# NeoDigito_Medio.net
KiCad netlist of a schematic drawn in EAGLE
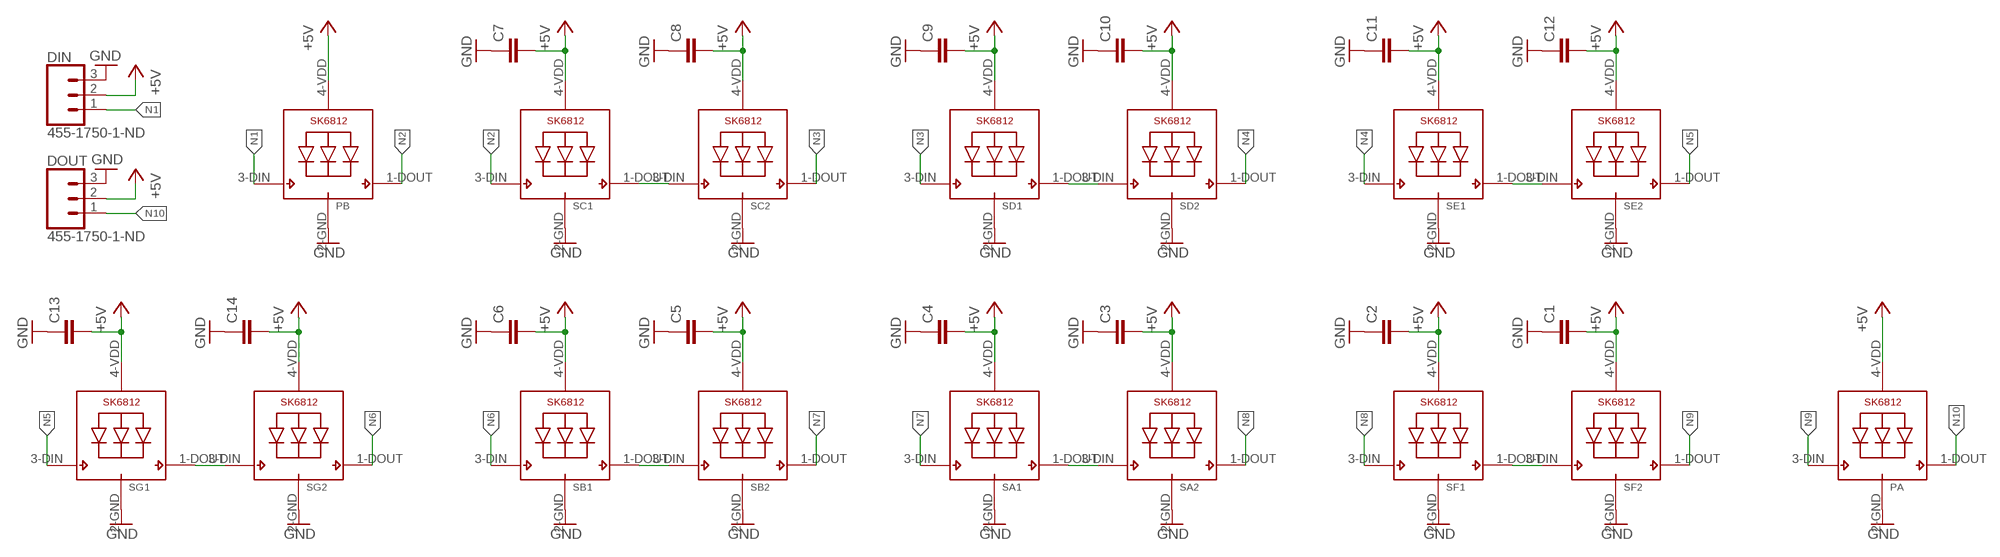
[diagram p0: schematic, sheet 1]

(export (version "E")
  (design (tool "Eeschema 10.0.6"))
  (components
    (comp (ref "C1")
      (value "C-EUC0805")
      (footprint "eagle-import:C0805")
      (libsource (lib "eagle-import") (part "C-EUC0805"))
    )
    (comp (ref "C2")
      (value "C-EUC0805")
      (footprint "eagle-import:C0805")
      (libsource (lib "eagle-import") (part "C-EUC0805"))
    )
    (comp (ref "C3")
      (value "C-EUC0805")
      (footprint "eagle-import:C0805")
      (libsource (lib "eagle-import") (part "C-EUC0805"))
    )
    (comp (ref "C4")
      (value "C-EUC0805")
      (footprint "eagle-import:C0805")
      (libsource (lib "eagle-import") (part "C-EUC0805"))
    )
    (comp (ref "C5")
      (value "C-EUC0805")
      (footprint "eagle-import:C0805")
      (libsource (lib "eagle-import") (part "C-EUC0805"))
    )
    (comp (ref "C6")
      (value "C-EUC0805")
      (footprint "eagle-import:C0805")
      (libsource (lib "eagle-import") (part "C-EUC0805"))
    )
    (comp (ref "C7")
      (value "C-EUC0805")
      (footprint "eagle-import:C0805")
      (libsource (lib "eagle-import") (part "C-EUC0805"))
    )
    (comp (ref "C8")
      (value "C-EUC0805")
      (footprint "eagle-import:C0805")
      (libsource (lib "eagle-import") (part "C-EUC0805"))
    )
    (comp (ref "C9")
      (value "C-EUC0805")
      (footprint "eagle-import:C0805")
      (libsource (lib "eagle-import") (part "C-EUC0805"))
    )
    (comp (ref "C10")
      (value "C-EUC0805")
      (footprint "eagle-import:C0805")
      (libsource (lib "eagle-import") (part "C-EUC0805"))
    )
    (comp (ref "C11")
      (value "C-EUC0805")
      (footprint "eagle-import:C0805")
      (libsource (lib "eagle-import") (part "C-EUC0805"))
    )
    (comp (ref "C12")
      (value "C-EUC0805")
      (footprint "eagle-import:C0805")
      (libsource (lib "eagle-import") (part "C-EUC0805"))
    )
    (comp (ref "C13")
      (value "C-EUC0805")
      (footprint "eagle-import:C0805")
      (libsource (lib "eagle-import") (part "C-EUC0805"))
    )
    (comp (ref "C14")
      (value "C-EUC0805")
      (footprint "eagle-import:C0805")
      (libsource (lib "eagle-import") (part "C-EUC0805"))
    )
    (comp (ref "DIN")
      (value "455-1750-1-ND")
      (footprint "eagle-import:1X03")
      (libsource (lib "eagle-import") (part "CONN_03"))
    )
    (comp (ref "DOUT")
      (value "455-1750-1-ND")
      (footprint "eagle-import:1X03_NO_SILK")
      (libsource (lib "eagle-import") (part "CONN_031X03_NO_SILK"))
    )
    (comp (ref "PA")
      (value "SK6812_3535")
      (footprint "eagle-import:LED3535")
      (libsource (lib "eagle-import") (part "SK6812_3535"))
    )
    (comp (ref "PB")
      (value "SK6812_3535")
      (footprint "eagle-import:LED3535")
      (libsource (lib "eagle-import") (part "SK6812_3535"))
    )
    (comp (ref "SA1")
      (value "SK6812_3535")
      (footprint "eagle-import:LED3535")
      (libsource (lib "eagle-import") (part "SK6812_3535"))
    )
    (comp (ref "SA2")
      (value "SK6812_3535")
      (footprint "eagle-import:LED3535")
      (libsource (lib "eagle-import") (part "SK6812_3535"))
    )
    (comp (ref "SB1")
      (value "SK6812_3535")
      (footprint "eagle-import:LED3535")
      (libsource (lib "eagle-import") (part "SK6812_3535"))
    )
    (comp (ref "SB2")
      (value "SK6812_3535")
      (footprint "eagle-import:LED3535")
      (libsource (lib "eagle-import") (part "SK6812_3535"))
    )
    (comp (ref "SC1")
      (value "SK6812_3535")
      (footprint "eagle-import:LED3535")
      (libsource (lib "eagle-import") (part "SK6812_3535"))
    )
    (comp (ref "SC2")
      (value "SK6812_3535")
      (footprint "eagle-import:LED3535")
      (libsource (lib "eagle-import") (part "SK6812_3535"))
    )
    (comp (ref "SD1")
      (value "SK6812_3535")
      (footprint "eagle-import:LED3535")
      (libsource (lib "eagle-import") (part "SK6812_3535"))
    )
    (comp (ref "SD2")
      (value "SK6812_3535")
      (footprint "eagle-import:LED3535")
      (libsource (lib "eagle-import") (part "SK6812_3535"))
    )
    (comp (ref "SE1")
      (value "SK6812_3535")
      (footprint "eagle-import:LED3535")
      (libsource (lib "eagle-import") (part "SK6812_3535"))
    )
    (comp (ref "SE2")
      (value "SK6812_3535")
      (footprint "eagle-import:LED3535")
      (libsource (lib "eagle-import") (part "SK6812_3535"))
    )
    (comp (ref "SF1")
      (value "SK6812_3535")
      (footprint "eagle-import:LED3535")
      (libsource (lib "eagle-import") (part "SK6812_3535"))
    )
    (comp (ref "SF2")
      (value "SK6812_3535")
      (footprint "eagle-import:LED3535")
      (libsource (lib "eagle-import") (part "SK6812_3535"))
    )
    (comp (ref "SG1")
      (value "SK6812_3535")
      (footprint "eagle-import:LED3535")
      (libsource (lib "eagle-import") (part "SK6812_3535"))
    )
    (comp (ref "SG2")
      (value "SK6812_3535")
      (footprint "eagle-import:LED3535")
      (libsource (lib "eagle-import") (part "SK6812_3535"))
    )
  )
  (nets
    (net (code "1") (name "+5V") (class "Default")
      (node (ref "C1") (pin "2") (pinfunction "2_2") (pintype "passive"))
      (node (ref "C10") (pin "2") (pinfunction "2_2") (pintype "passive"))
      (node (ref "C11") (pin "2") (pinfunction "2_2") (pintype "passive"))
      (node (ref "C12") (pin "2") (pinfunction "2_2") (pintype "passive"))
      (node (ref "C13") (pin "2") (pinfunction "2_2") (pintype "passive"))
      (node (ref "C14") (pin "2") (pinfunction "2_2") (pintype "passive"))
      (node (ref "C2") (pin "2") (pinfunction "2_2") (pintype "passive"))
      (node (ref "C3") (pin "2") (pinfunction "2_2") (pintype "passive"))
      (node (ref "C4") (pin "2") (pinfunction "2_2") (pintype "passive"))
      (node (ref "C5") (pin "2") (pinfunction "2_2") (pintype "passive"))
      (node (ref "C6") (pin "2") (pinfunction "2_2") (pintype "passive"))
      (node (ref "C7") (pin "2") (pinfunction "2_2") (pintype "passive"))
      (node (ref "C8") (pin "2") (pinfunction "2_2") (pintype "passive"))
      (node (ref "C9") (pin "2") (pinfunction "2_2") (pintype "passive"))
      (node (ref "DIN") (pin "2") (pinfunction "2_2") (pintype "passive"))
      (node (ref "DOUT") (pin "2") (pinfunction "2_2") (pintype "passive"))
      (node (ref "PA") (pin "4-VDD") (pinfunction "VDD_4-VDD") (pintype "power_in"))
      (node (ref "PB") (pin "4-VDD") (pinfunction "VDD_4-VDD") (pintype "power_in"))
      (node (ref "SA1") (pin "4-VDD") (pinfunction "VDD_4-VDD") (pintype "power_in"))
      (node (ref "SA2") (pin "4-VDD") (pinfunction "VDD_4-VDD") (pintype "power_in"))
      (node (ref "SB1") (pin "4-VDD") (pinfunction "VDD_4-VDD") (pintype "power_in"))
      (node (ref "SB2") (pin "4-VDD") (pinfunction "VDD_4-VDD") (pintype "power_in"))
      (node (ref "SC1") (pin "4-VDD") (pinfunction "VDD_4-VDD") (pintype "power_in"))
      (node (ref "SC2") (pin "4-VDD") (pinfunction "VDD_4-VDD") (pintype "power_in"))
      (node (ref "SD1") (pin "4-VDD") (pinfunction "VDD_4-VDD") (pintype "power_in"))
      (node (ref "SD2") (pin "4-VDD") (pinfunction "VDD_4-VDD") (pintype "power_in"))
      (node (ref "SE1") (pin "4-VDD") (pinfunction "VDD_4-VDD") (pintype "power_in"))
      (node (ref "SE2") (pin "4-VDD") (pinfunction "VDD_4-VDD") (pintype "power_in"))
      (node (ref "SF1") (pin "4-VDD") (pinfunction "VDD_4-VDD") (pintype "power_in"))
      (node (ref "SF2") (pin "4-VDD") (pinfunction "VDD_4-VDD") (pintype "power_in"))
      (node (ref "SG1") (pin "4-VDD") (pinfunction "VDD_4-VDD") (pintype "power_in"))
      (node (ref "SG2") (pin "4-VDD") (pinfunction "VDD_4-VDD") (pintype "power_in"))
    )
    (net (code "2") (name "GND") (class "Default")
      (node (ref "C1") (pin "1") (pinfunction "1_1") (pintype "passive"))
      (node (ref "C10") (pin "1") (pinfunction "1_1") (pintype "passive"))
      (node (ref "C11") (pin "1") (pinfunction "1_1") (pintype "passive"))
      (node (ref "C12") (pin "1") (pinfunction "1_1") (pintype "passive"))
      (node (ref "C13") (pin "1") (pinfunction "1_1") (pintype "passive"))
      (node (ref "C14") (pin "1") (pinfunction "1_1") (pintype "passive"))
      (node (ref "C2") (pin "1") (pinfunction "1_1") (pintype "passive"))
      (node (ref "C3") (pin "1") (pinfunction "1_1") (pintype "passive"))
      (node (ref "C4") (pin "1") (pinfunction "1_1") (pintype "passive"))
      (node (ref "C5") (pin "1") (pinfunction "1_1") (pintype "passive"))
      (node (ref "C6") (pin "1") (pinfunction "1_1") (pintype "passive"))
      (node (ref "C7") (pin "1") (pinfunction "1_1") (pintype "passive"))
      (node (ref "C8") (pin "1") (pinfunction "1_1") (pintype "passive"))
      (node (ref "C9") (pin "1") (pinfunction "1_1") (pintype "passive"))
      (node (ref "DIN") (pin "3") (pinfunction "3_3") (pintype "passive"))
      (node (ref "DOUT") (pin "3") (pinfunction "3_3") (pintype "passive"))
      (node (ref "PA") (pin "2-GND") (pinfunction "GND_2-GND") (pintype "power_in"))
      (node (ref "PB") (pin "2-GND") (pinfunction "GND_2-GND") (pintype "power_in"))
      (node (ref "SA1") (pin "2-GND") (pinfunction "GND_2-GND") (pintype "power_in"))
      (node (ref "SA2") (pin "2-GND") (pinfunction "GND_2-GND") (pintype "power_in"))
      (node (ref "SB1") (pin "2-GND") (pinfunction "GND_2-GND") (pintype "power_in"))
      (node (ref "SB2") (pin "2-GND") (pinfunction "GND_2-GND") (pintype "power_in"))
      (node (ref "SC1") (pin "2-GND") (pinfunction "GND_2-GND") (pintype "power_in"))
      (node (ref "SC2") (pin "2-GND") (pinfunction "GND_2-GND") (pintype "power_in"))
      (node (ref "SD1") (pin "2-GND") (pinfunction "GND_2-GND") (pintype "power_in"))
      (node (ref "SD2") (pin "2-GND") (pinfunction "GND_2-GND") (pintype "power_in"))
      (node (ref "SE1") (pin "2-GND") (pinfunction "GND_2-GND") (pintype "power_in"))
      (node (ref "SE2") (pin "2-GND") (pinfunction "GND_2-GND") (pintype "power_in"))
      (node (ref "SF1") (pin "2-GND") (pinfunction "GND_2-GND") (pintype "power_in"))
      (node (ref "SF2") (pin "2-GND") (pinfunction "GND_2-GND") (pintype "power_in"))
      (node (ref "SG1") (pin "2-GND") (pinfunction "GND_2-GND") (pintype "power_in"))
      (node (ref "SG2") (pin "2-GND") (pinfunction "GND_2-GND") (pintype "power_in"))
    )
    (net (code "3") (name "N1") (class "Default")
      (node (ref "DIN") (pin "1") (pinfunction "1_1") (pintype "passive"))
      (node (ref "PB") (pin "3-DIN") (pinfunction "DI_3-DIN") (pintype "input"))
    )
    (net (code "4") (name "N2") (class "Default")
      (node (ref "PB") (pin "1-DOUT") (pinfunction "DO_1-DOUT") (pintype "output"))
      (node (ref "SC1") (pin "3-DIN") (pinfunction "DI_3-DIN") (pintype "input"))
    )
    (net (code "5") (name "N3") (class "Default")
      (node (ref "SC2") (pin "1-DOUT") (pinfunction "DO_1-DOUT") (pintype "output"))
      (node (ref "SD1") (pin "3-DIN") (pinfunction "DI_3-DIN") (pintype "input"))
    )
    (net (code "6") (name "N4") (class "Default")
      (node (ref "SD2") (pin "1-DOUT") (pinfunction "DO_1-DOUT") (pintype "output"))
      (node (ref "SE1") (pin "3-DIN") (pinfunction "DI_3-DIN") (pintype "input"))
    )
    (net (code "7") (name "N5") (class "Default")
      (node (ref "SE2") (pin "1-DOUT") (pinfunction "DO_1-DOUT") (pintype "output"))
      (node (ref "SG1") (pin "3-DIN") (pinfunction "DI_3-DIN") (pintype "input"))
    )
    (net (code "8") (name "N6") (class "Default")
      (node (ref "SB1") (pin "3-DIN") (pinfunction "DI_3-DIN") (pintype "input"))
      (node (ref "SG2") (pin "1-DOUT") (pinfunction "DO_1-DOUT") (pintype "output"))
    )
    (net (code "9") (name "N7") (class "Default")
      (node (ref "SA1") (pin "3-DIN") (pinfunction "DI_3-DIN") (pintype "input"))
      (node (ref "SB2") (pin "1-DOUT") (pinfunction "DO_1-DOUT") (pintype "output"))
    )
    (net (code "10") (name "N8") (class "Default")
      (node (ref "SA2") (pin "1-DOUT") (pinfunction "DO_1-DOUT") (pintype "output"))
      (node (ref "SF1") (pin "3-DIN") (pinfunction "DI_3-DIN") (pintype "input"))
    )
    (net (code "11") (name "N9") (class "Default")
      (node (ref "PA") (pin "3-DIN") (pinfunction "DI_3-DIN") (pintype "input"))
      (node (ref "SF2") (pin "1-DOUT") (pinfunction "DO_1-DOUT") (pintype "output"))
    )
    (net (code "12") (name "N10") (class "Default")
      (node (ref "DOUT") (pin "1") (pinfunction "1_1") (pintype "passive"))
      (node (ref "PA") (pin "1-DOUT") (pinfunction "DO_1-DOUT") (pintype "output"))
    )
    (net (code "13") (name "Net-(SA1-DO)") (class "Default")
      (node (ref "SA1") (pin "1-DOUT") (pinfunction "DO_1-DOUT") (pintype "output"))
      (node (ref "SA2") (pin "3-DIN") (pinfunction "DI_3-DIN") (pintype "input"))
    )
    (net (code "14") (name "Net-(SB1-DO)") (class "Default")
      (node (ref "SB1") (pin "1-DOUT") (pinfunction "DO_1-DOUT") (pintype "output"))
      (node (ref "SB2") (pin "3-DIN") (pinfunction "DI_3-DIN") (pintype "input"))
    )
    (net (code "15") (name "Net-(SC1-DO)") (class "Default")
      (node (ref "SC1") (pin "1-DOUT") (pinfunction "DO_1-DOUT") (pintype "output"))
      (node (ref "SC2") (pin "3-DIN") (pinfunction "DI_3-DIN") (pintype "input"))
    )
    (net (code "16") (name "Net-(SD1-DO)") (class "Default")
      (node (ref "SD1") (pin "1-DOUT") (pinfunction "DO_1-DOUT") (pintype "output"))
      (node (ref "SD2") (pin "3-DIN") (pinfunction "DI_3-DIN") (pintype "input"))
    )
    (net (code "17") (name "Net-(SE1-DO)") (class "Default")
      (node (ref "SE1") (pin "1-DOUT") (pinfunction "DO_1-DOUT") (pintype "output"))
      (node (ref "SE2") (pin "3-DIN") (pinfunction "DI_3-DIN") (pintype "input"))
    )
    (net (code "18") (name "Net-(SF1-DO)") (class "Default")
      (node (ref "SF1") (pin "1-DOUT") (pinfunction "DO_1-DOUT") (pintype "output"))
      (node (ref "SF2") (pin "3-DIN") (pinfunction "DI_3-DIN") (pintype "input"))
    )
    (net (code "19") (name "Net-(SG1-DO)") (class "Default")
      (node (ref "SG1") (pin "1-DOUT") (pinfunction "DO_1-DOUT") (pintype "output"))
      (node (ref "SG2") (pin "3-DIN") (pinfunction "DI_3-DIN") (pintype "input"))
    )
  )
)
